# Placa_alimentacion.net
KiCad netlist of a schematic drawn in EAGLE
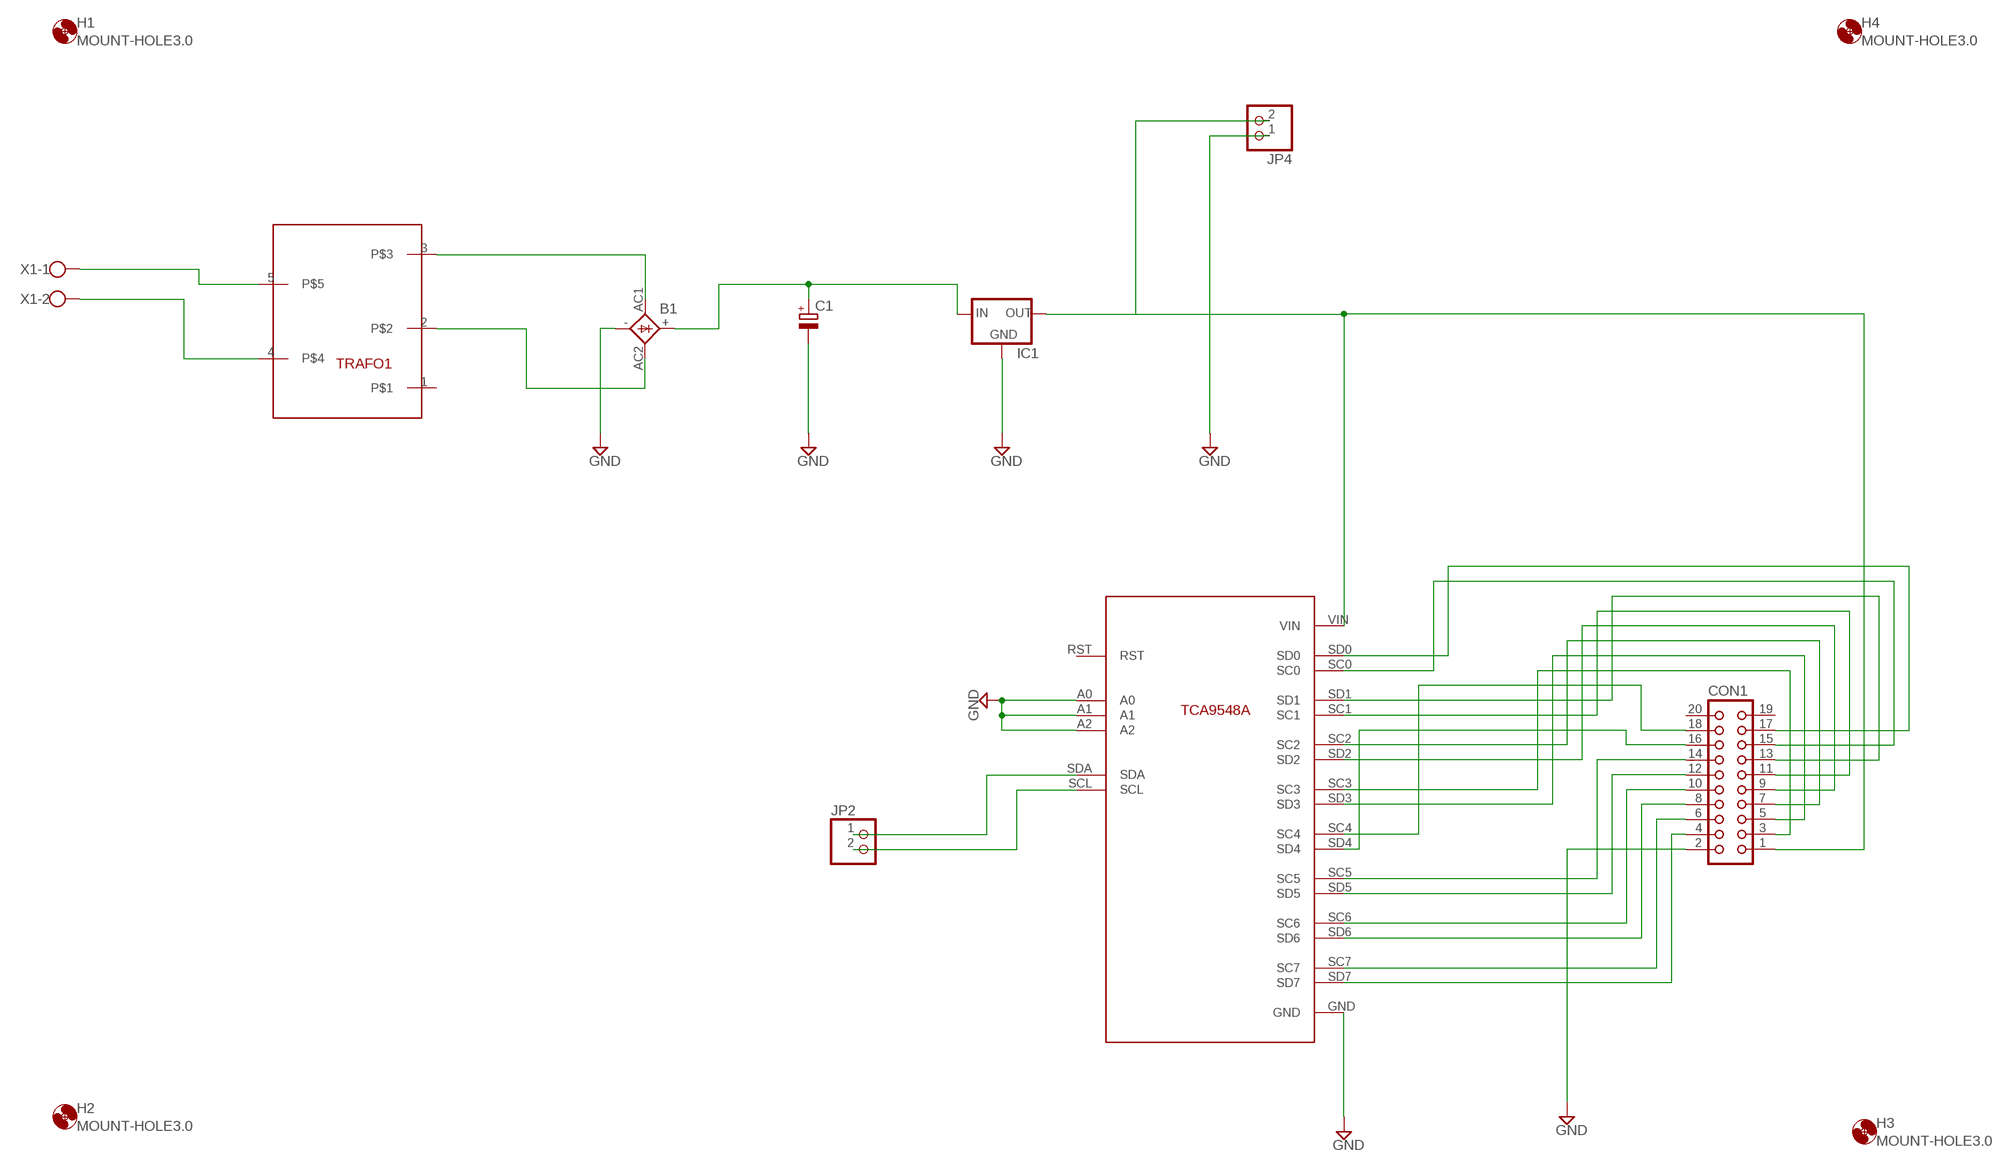
[diagram p0: schematic, sheet 1]

(export (version "E")
  (design (tool "Eeschema 10.0.6"))
  (components
    (comp (ref "B1")
      (value "KBU")
      (footprint "eagle-import:KBU")
      (libsource (lib "eagle-import") (part "KBU"))
    )
    (comp (ref "C1")
      (value "CPOL-EUE5-8.5")
      (footprint "eagle-import:E5-8,5")
      (libsource (lib "eagle-import") (part "CPOL-EUE5-8.5"))
    )
    (comp (ref "CON1")
      (value "CON20")
      (footprint "eagle-import:CON20")
      (libsource (lib "eagle-import") (part "CON20"))
    )
    (comp (ref "H1")
      (value "MOUNT-HOLE3.0")
      (footprint "eagle-import:3,0")
      (libsource (lib "eagle-import") (part "MOUNT-HOLE3.0"))
    )
    (comp (ref "H2")
      (value "MOUNT-HOLE3.0")
      (footprint "eagle-import:3,0")
      (libsource (lib "eagle-import") (part "MOUNT-HOLE3.0"))
    )
    (comp (ref "H3")
      (value "MOUNT-HOLE3.0")
      (footprint "eagle-import:3,0")
      (libsource (lib "eagle-import") (part "MOUNT-HOLE3.0"))
    )
    (comp (ref "H4")
      (value "MOUNT-HOLE3.0")
      (footprint "eagle-import:3,0")
      (libsource (lib "eagle-import") (part "MOUNT-HOLE3.0"))
    )
    (comp (ref "IC1")
      (value "78MXXL")
      (footprint "eagle-import:78MXXL")
      (libsource (lib "eagle-import") (part "78MXXL"))
    )
    (comp (ref "JP2")
      (value "PINHD-1X2")
      (footprint "eagle-import:1X02")
      (libsource (lib "eagle-import") (part "PINHD-1X2"))
    )
    (comp (ref "JP4")
      (value "PINHD-1X2")
      (footprint "eagle-import:1X02")
      (libsource (lib "eagle-import") (part "PINHD-1X2"))
    )
    (comp (ref "TRAFO1")
      (value "ARISTON_TR5309")
      (footprint "eagle-import:ARISTON_TR5309")
      (libsource (lib "eagle-import") (part "ARISTON_TR5309"))
    )
    (comp (ref "U$1")
      (value "TCA9548A")
      (footprint "eagle-import:TCA9548A")
      (libsource (lib "eagle-import") (part "TCA9548A"))
    )
    (comp (ref "X1")
      (value "W237-102")
      (footprint "eagle-import:W237-102")
      (fields (field (name "MPN") "237-102"))
      (libsource (lib "eagle-import") (part "W237-102"))
    )
  )
  (nets
    (net (code "1") (name "GND") (class "Default")
      (node (ref "B1") (pin "-") (pinfunction "-_-") (pintype "passive"))
      (node (ref "C1") (pin "-") (pinfunction "-_-") (pintype "passive"))
      (node (ref "CON1") (pin "2") (pinfunction "2_2") (pintype "passive"))
      (node (ref "IC1") (pin "GND") (pinfunction "GND_GND") (pintype "input"))
      (node (ref "JP4") (pin "1") (pinfunction "1_1") (pintype "passive"))
      (node (ref "U$1") (pin "A0") (pinfunction "A0_A0") (pintype "bidirectional"))
      (node (ref "U$1") (pin "A1") (pinfunction "A1_A1") (pintype "bidirectional"))
      (node (ref "U$1") (pin "A2") (pinfunction "A2_A2") (pintype "bidirectional"))
      (node (ref "U$1") (pin "GND") (pinfunction "GND_GND") (pintype "bidirectional"))
    )
    (net (code "2") (name "Net-(B1-Pad+)") (class "Default")
      (node (ref "B1") (pin "+") (pinfunction "+_+") (pintype "passive"))
      (node (ref "C1") (pin "+") (pinfunction "+_+") (pintype "passive"))
      (node (ref "IC1") (pin "IN") (pinfunction "IN_IN") (pintype "input"))
    )
    (net (code "3") (name "Net-(CON1-Pad1)") (class "Default")
      (node (ref "CON1") (pin "1") (pinfunction "1_1") (pintype "passive"))
      (node (ref "IC1") (pin "OUT") (pinfunction "OUT_OUT") (pintype "passive"))
      (node (ref "JP4") (pin "2") (pinfunction "2_2") (pintype "passive"))
      (node (ref "U$1") (pin "VIN") (pinfunction "VIN_VIN") (pintype "bidirectional"))
    )
    (net (code "4") (name "Net-(CON1-Pad3)") (class "Default")
      (node (ref "CON1") (pin "3") (pinfunction "3_3") (pintype "passive"))
      (node (ref "U$1") (pin "SC3") (pinfunction "SC3_SC3") (pintype "bidirectional"))
    )
    (net (code "5") (name "Net-(CON1-Pad4)") (class "Default")
      (node (ref "CON1") (pin "4") (pinfunction "4_4") (pintype "passive"))
      (node (ref "U$1") (pin "SD7") (pinfunction "SD7_SD7") (pintype "bidirectional"))
    )
    (net (code "6") (name "Net-(CON1-Pad5)") (class "Default")
      (node (ref "CON1") (pin "5") (pinfunction "5_5") (pintype "passive"))
      (node (ref "U$1") (pin "SD3") (pinfunction "SD3_SD3") (pintype "bidirectional"))
    )
    (net (code "7") (name "Net-(CON1-Pad6)") (class "Default")
      (node (ref "CON1") (pin "6") (pinfunction "6_6") (pintype "passive"))
      (node (ref "U$1") (pin "SC7") (pinfunction "SC7_SC7") (pintype "bidirectional"))
    )
    (net (code "8") (name "Net-(CON1-Pad7)") (class "Default")
      (node (ref "CON1") (pin "7") (pinfunction "7_7") (pintype "passive"))
      (node (ref "U$1") (pin "SC2") (pinfunction "SC2_SC2") (pintype "bidirectional"))
    )
    (net (code "9") (name "Net-(CON1-Pad8)") (class "Default")
      (node (ref "CON1") (pin "8") (pinfunction "8_8") (pintype "passive"))
      (node (ref "U$1") (pin "SD6") (pinfunction "SD6_SD6") (pintype "bidirectional"))
    )
    (net (code "10") (name "Net-(CON1-Pad9)") (class "Default")
      (node (ref "CON1") (pin "9") (pinfunction "9_9") (pintype "passive"))
      (node (ref "U$1") (pin "SD2") (pinfunction "SD2_SD2") (pintype "bidirectional"))
    )
    (net (code "11") (name "Net-(CON1-Pad10)") (class "Default")
      (node (ref "CON1") (pin "10") (pinfunction "10_10") (pintype "passive"))
      (node (ref "U$1") (pin "SC6") (pinfunction "SC6_SC6") (pintype "bidirectional"))
    )
    (net (code "12") (name "Net-(CON1-Pad11)") (class "Default")
      (node (ref "CON1") (pin "11") (pinfunction "11_11") (pintype "passive"))
      (node (ref "U$1") (pin "SC1") (pinfunction "SC1_SC1") (pintype "bidirectional"))
    )
    (net (code "13") (name "Net-(CON1-Pad12)") (class "Default")
      (node (ref "CON1") (pin "12") (pinfunction "12_12") (pintype "passive"))
      (node (ref "U$1") (pin "SD5") (pinfunction "SD5_SD5") (pintype "bidirectional"))
    )
    (net (code "14") (name "Net-(CON1-Pad13)") (class "Default")
      (node (ref "CON1") (pin "13") (pinfunction "13_13") (pintype "passive"))
      (node (ref "U$1") (pin "SD1") (pinfunction "SD1_SD1") (pintype "bidirectional"))
    )
    (net (code "15") (name "Net-(CON1-Pad14)") (class "Default")
      (node (ref "CON1") (pin "14") (pinfunction "14_14") (pintype "passive"))
      (node (ref "U$1") (pin "SC5") (pinfunction "SC5_SC5") (pintype "bidirectional"))
    )
    (net (code "16") (name "Net-(CON1-Pad15)") (class "Default")
      (node (ref "CON1") (pin "15") (pinfunction "15_15") (pintype "passive"))
      (node (ref "U$1") (pin "SC0") (pinfunction "SC0_SC0") (pintype "bidirectional"))
    )
    (net (code "17") (name "Net-(CON1-Pad16)") (class "Default")
      (node (ref "CON1") (pin "16") (pinfunction "16_16") (pintype "passive"))
      (node (ref "U$1") (pin "SD4") (pinfunction "SD4_SD4") (pintype "bidirectional"))
    )
    (net (code "18") (name "Net-(CON1-Pad17)") (class "Default")
      (node (ref "CON1") (pin "17") (pinfunction "17_17") (pintype "passive"))
      (node (ref "U$1") (pin "SD0") (pinfunction "SD0_SD0") (pintype "bidirectional"))
    )
    (net (code "19") (name "Net-(CON1-Pad18)") (class "Default")
      (node (ref "CON1") (pin "18") (pinfunction "18_18") (pintype "passive"))
      (node (ref "U$1") (pin "SC4") (pinfunction "SC4_SC4") (pintype "bidirectional"))
    )
    (net (code "20") (name "Net-(JP2-Pad1)") (class "Default")
      (node (ref "JP2") (pin "1") (pinfunction "1_1") (pintype "passive"))
      (node (ref "U$1") (pin "SDA") (pinfunction "SDA_SDA") (pintype "bidirectional"))
    )
    (net (code "21") (name "Net-(JP2-Pad2)") (class "Default")
      (node (ref "JP2") (pin "2") (pinfunction "2_2") (pintype "passive"))
      (node (ref "U$1") (pin "SCL") (pinfunction "SCL_SCL") (pintype "bidirectional"))
    )
    (net (code "22") (name "Net-(TRAFO1-P$2)") (class "Default")
      (node (ref "B1") (pin "AC2") (pinfunction "AC2_AC2") (pintype "passive"))
      (node (ref "TRAFO1") (pin "2") (pinfunction "P$2_2") (pintype "bidirectional"))
    )
    (net (code "23") (name "Net-(TRAFO1-P$3)") (class "Default")
      (node (ref "B1") (pin "AC1") (pinfunction "AC1_AC1") (pintype "passive"))
      (node (ref "TRAFO1") (pin "3") (pinfunction "P$3_3") (pintype "bidirectional"))
    )
    (net (code "24") (name "Net-(TRAFO1-P$4)") (class "Default")
      (node (ref "TRAFO1") (pin "4") (pinfunction "P$4_4") (pintype "bidirectional"))
      (node (ref "X1") (pin "2") (pinfunction "KL_2") (pintype "passive"))
    )
    (net (code "25") (name "Net-(TRAFO1-P$5)") (class "Default")
      (node (ref "TRAFO1") (pin "5") (pinfunction "P$5_5") (pintype "bidirectional"))
      (node (ref "X1") (pin "1") (pinfunction "KL_1") (pintype "passive"))
    )
    (net (code "26") (name "unconnected-(CON1-Pad19)") (class "Default")
      (node (ref "CON1") (pin "19") (pinfunction "19_19") (pintype "passive"))
    )
    (net (code "27") (name "unconnected-(CON1-Pad20)") (class "Default")
      (node (ref "CON1") (pin "20") (pinfunction "20_20") (pintype "passive"))
    )
    (net (code "28") (name "unconnected-(TRAFO1-P$1-Pad1)") (class "Default")
      (node (ref "TRAFO1") (pin "1") (pinfunction "P$1_1") (pintype "bidirectional"))
    )
    (net (code "29") (name "unconnected-(U$1-PadRST)") (class "Default")
      (node (ref "U$1") (pin "RST") (pinfunction "RST_RST") (pintype "bidirectional"))
    )
  )
)
